# Fluke_PM9080_RS232.net
KiCad netlist of a schematic drawn in EAGLE
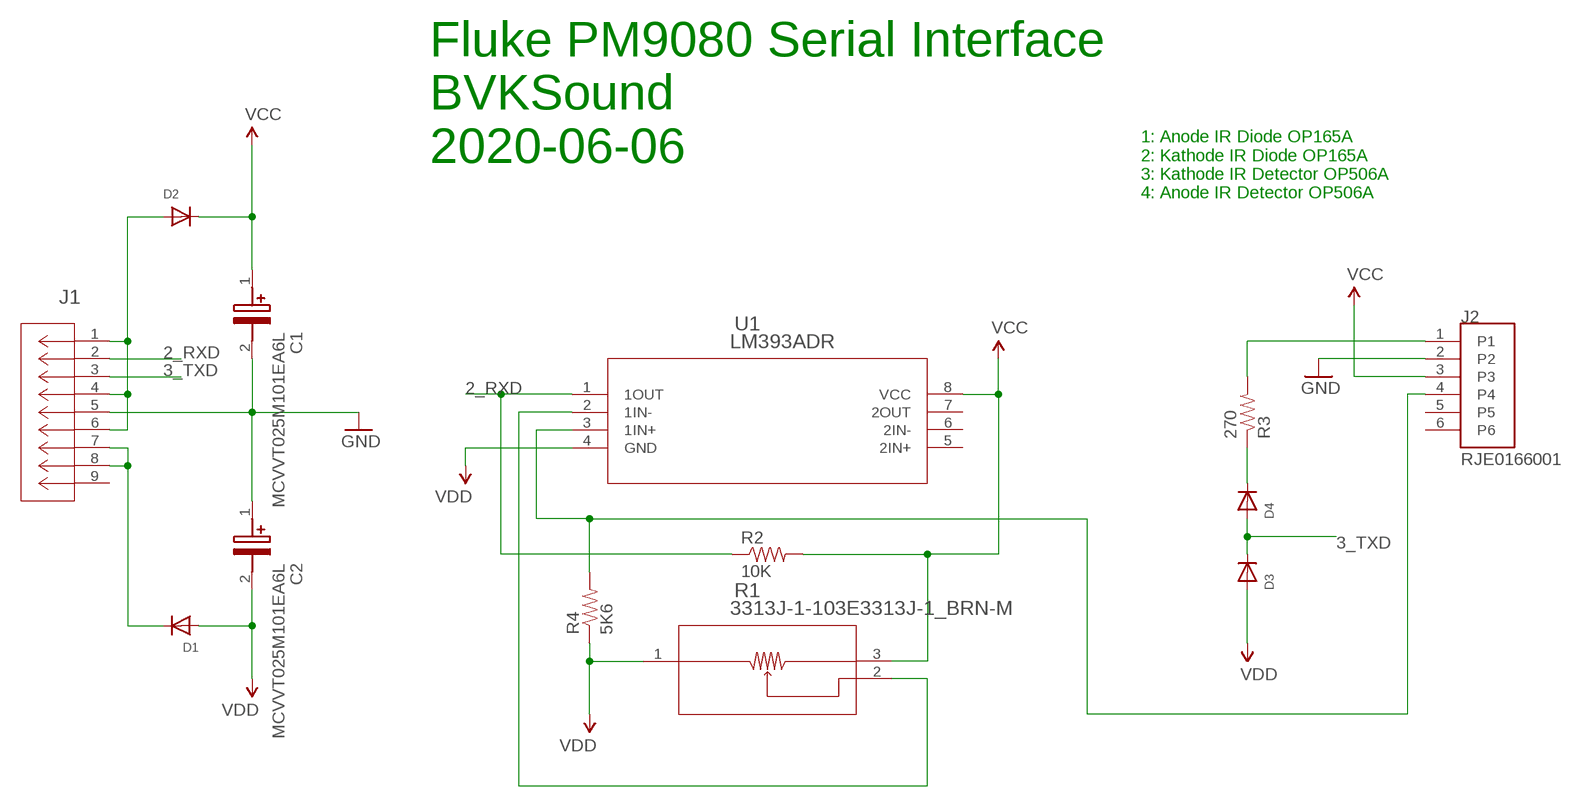
[diagram p0: schematic, sheet 1]

(export (version "E")
  (design (tool "Eeschema 10.0.6"))
  (components
    (comp (ref "C1")
      (value "MCVVT025M101EA6L")
      (footprint "eagle-import:CAPAE830X1060N")
      (libsource (lib "eagle-import") (part "MCVVT025M101EA6L"))
    )
    (comp (ref "C2")
      (value "MCVVT025M101EA6L")
      (footprint "eagle-import:CAPAE830X1060N")
      (libsource (lib "eagle-import") (part "MCVVT025M101EA6L"))
    )
    (comp (ref "D1")
      (value "DIODESOD-123")
      (footprint "eagle-import:SOD-123")
      (libsource (lib "eagle-import") (part "DIODESOD-123"))
    )
    (comp (ref "D2")
      (value "DIODESOD-123")
      (footprint "eagle-import:SOD-123")
      (libsource (lib "eagle-import") (part "DIODESOD-123"))
    )
    (comp (ref "D3")
      (value "DIODESOD-123")
      (footprint "eagle-import:SOD-123")
      (libsource (lib "eagle-import") (part "DIODESOD-123"))
    )
    (comp (ref "D4")
      (value "DIODESOD-123")
      (footprint "eagle-import:SOD-123")
      (libsource (lib "eagle-import") (part "DIODESOD-123"))
    )
    (comp (ref "J1")
      (value "5747844-6")
      (footprint "eagle-import:CONN_5747844-6_TYC")
      (libsource (lib "eagle-import") (part "5747844-6"))
    )
    (comp (ref "J2")
      (value "RJE0166001")
      (footprint "eagle-import:AMPHENOL_RJE0166001")
      (fields (field (name "MF") "Amphenol ICC"))
      (libsource (lib "eagle-import") (part "RJE0166001"))
    )
    (comp (ref "R1")
      (value "3313J-1-103E3313J-1_BRN-M")
      (footprint "eagle-import:3313J-1_BRN-M")
      (fields
        (field (name "MANUFACTURER_PART_NUMBER") "3313J-1-103E")
        (field (name "COPYRIGHT") "Copyright (C) 2018 Accelerated Designs. All rights reserved")
      )
      (libsource (lib "eagle-import") (part "3313J-1-103E3313J-1_BRN-M"))
    )
    (comp (ref "R2")
      (value "10K")
      (footprint "eagle-import:1206")
      (libsource (lib "eagle-import") (part "RESISTOR1206"))
    )
    (comp (ref "R3")
      (value "270")
      (footprint "eagle-import:1206")
      (libsource (lib "eagle-import") (part "RESISTOR1206"))
    )
    (comp (ref "R4")
      (value "5K6")
      (footprint "eagle-import:1206")
      (libsource (lib "eagle-import") (part "RESISTOR1206"))
    )
    (comp (ref "U1")
      (value "LM393ADR")
      (footprint "eagle-import:D8")
      (fields (field (name "MANUFACTURER") "Texas Instruments"))
      (libsource (lib "eagle-import") (part "LM393ADR"))
    )
  )
  (nets
    (net (code "1") (name "/2_RXD") (class "Default")
      (node (ref "J1") (pin "2") (pinfunction "2_2") (pintype "passive"))
      (node (ref "R2") (pin "1") (pinfunction "1_1") (pintype "passive"))
      (node (ref "U1") (pin "1") (pinfunction "1OUT_1") (pintype "output"))
    )
    (net (code "2") (name "/3_TXD") (class "Default")
      (node (ref "D3") (pin "C") (pinfunction "C_C") (pintype "passive"))
      (node (ref "D4") (pin "A") (pinfunction "A_A") (pintype "passive"))
      (node (ref "J1") (pin "3") (pinfunction "3_3") (pintype "passive"))
    )
    (net (code "3") (name "GND") (class "Default")
      (node (ref "C1") (pin "2") (pinfunction "-_2") (pintype "power_in"))
      (node (ref "C2") (pin "1") (pinfunction "+_1") (pintype "power_in"))
      (node (ref "J1") (pin "5") (pinfunction "5_5") (pintype "passive"))
      (node (ref "J2") (pin "2") (pinfunction "P2_2") (pintype "passive"))
    )
    (net (code "4") (name "Net-(D1-PadC)") (class "Default")
      (node (ref "D1") (pin "C") (pinfunction "C_C") (pintype "passive"))
      (node (ref "J1") (pin "7") (pinfunction "7_7") (pintype "passive"))
      (node (ref "J1") (pin "8") (pinfunction "8_8") (pintype "passive"))
    )
    (net (code "5") (name "Net-(D2-PadA)") (class "Default")
      (node (ref "D2") (pin "A") (pinfunction "A_A") (pintype "passive"))
      (node (ref "J1") (pin "1") (pinfunction "1_1") (pintype "passive"))
      (node (ref "J1") (pin "4") (pinfunction "4_4") (pintype "passive"))
      (node (ref "J1") (pin "6") (pinfunction "6_6") (pintype "passive"))
    )
    (net (code "6") (name "Net-(D4-PadC)") (class "Default")
      (node (ref "D4") (pin "C") (pinfunction "C_C") (pintype "passive"))
      (node (ref "R3") (pin "1") (pinfunction "1_1") (pintype "passive"))
    )
    (net (code "7") (name "Net-(J2-P1)") (class "Default")
      (node (ref "J2") (pin "1") (pinfunction "P1_1") (pintype "passive"))
      (node (ref "R3") (pin "2") (pinfunction "2_2") (pintype "passive"))
    )
    (net (code "8") (name "Net-(J2-P4)") (class "Default")
      (node (ref "J2") (pin "4") (pinfunction "P4_4") (pintype "passive"))
      (node (ref "R4") (pin "2") (pinfunction "2_2") (pintype "passive"))
      (node (ref "U1") (pin "3") (pinfunction "1IN+_3") (pintype "input"))
    )
    (net (code "9") (name "Net-(U1-1IN-)") (class "Default")
      (node (ref "R1") (pin "2") (pinfunction "2_2") (pintype "passive"))
      (node (ref "U1") (pin "2") (pinfunction "1IN-_2") (pintype "input"))
    )
    (net (code "10") (name "VCC") (class "Default")
      (node (ref "C1") (pin "1") (pinfunction "+_1") (pintype "power_in"))
      (node (ref "D2") (pin "C") (pinfunction "C_C") (pintype "passive"))
      (node (ref "J2") (pin "3") (pinfunction "P3_3") (pintype "passive"))
      (node (ref "R1") (pin "3") (pinfunction "3_3") (pintype "passive"))
      (node (ref "R2") (pin "2") (pinfunction "2_2") (pintype "passive"))
      (node (ref "U1") (pin "8") (pinfunction "VCC_8") (pintype "power_in"))
    )
    (net (code "11") (name "VDD") (class "Default")
      (node (ref "C2") (pin "2") (pinfunction "-_2") (pintype "power_in"))
      (node (ref "D1") (pin "A") (pinfunction "A_A") (pintype "passive"))
      (node (ref "D3") (pin "A") (pinfunction "A_A") (pintype "passive"))
      (node (ref "R1") (pin "1") (pinfunction "1_1") (pintype "passive"))
      (node (ref "R4") (pin "1") (pinfunction "1_1") (pintype "passive"))
      (node (ref "U1") (pin "4") (pinfunction "GND_4") (pintype "power_in"))
    )
    (net (code "12") (name "unconnected-(J1-Pad9)") (class "Default")
      (node (ref "J1") (pin "9") (pinfunction "9_9") (pintype "passive"))
    )
    (net (code "13") (name "unconnected-(J2-P5-Pad5)") (class "Default")
      (node (ref "J2") (pin "5") (pinfunction "P5_5") (pintype "passive"))
    )
    (net (code "14") (name "unconnected-(J2-P6-Pad6)") (class "Default")
      (node (ref "J2") (pin "6") (pinfunction "P6_6") (pintype "passive"))
    )
    (net (code "15") (name "unconnected-(U1-2IN+-Pad5)") (class "Default")
      (node (ref "U1") (pin "5") (pinfunction "2IN+_5") (pintype "input"))
    )
    (net (code "16") (name "unconnected-(U1-2IN--Pad6)") (class "Default")
      (node (ref "U1") (pin "6") (pinfunction "2IN-_6") (pintype "input"))
    )
    (net (code "17") (name "unconnected-(U1-2OUT-Pad7)") (class "Default")
      (node (ref "U1") (pin "7") (pinfunction "2OUT_7") (pintype "output"))
    )
  )
)
